# RF_Test.net
KiCad netlist of a schematic drawn in EAGLE
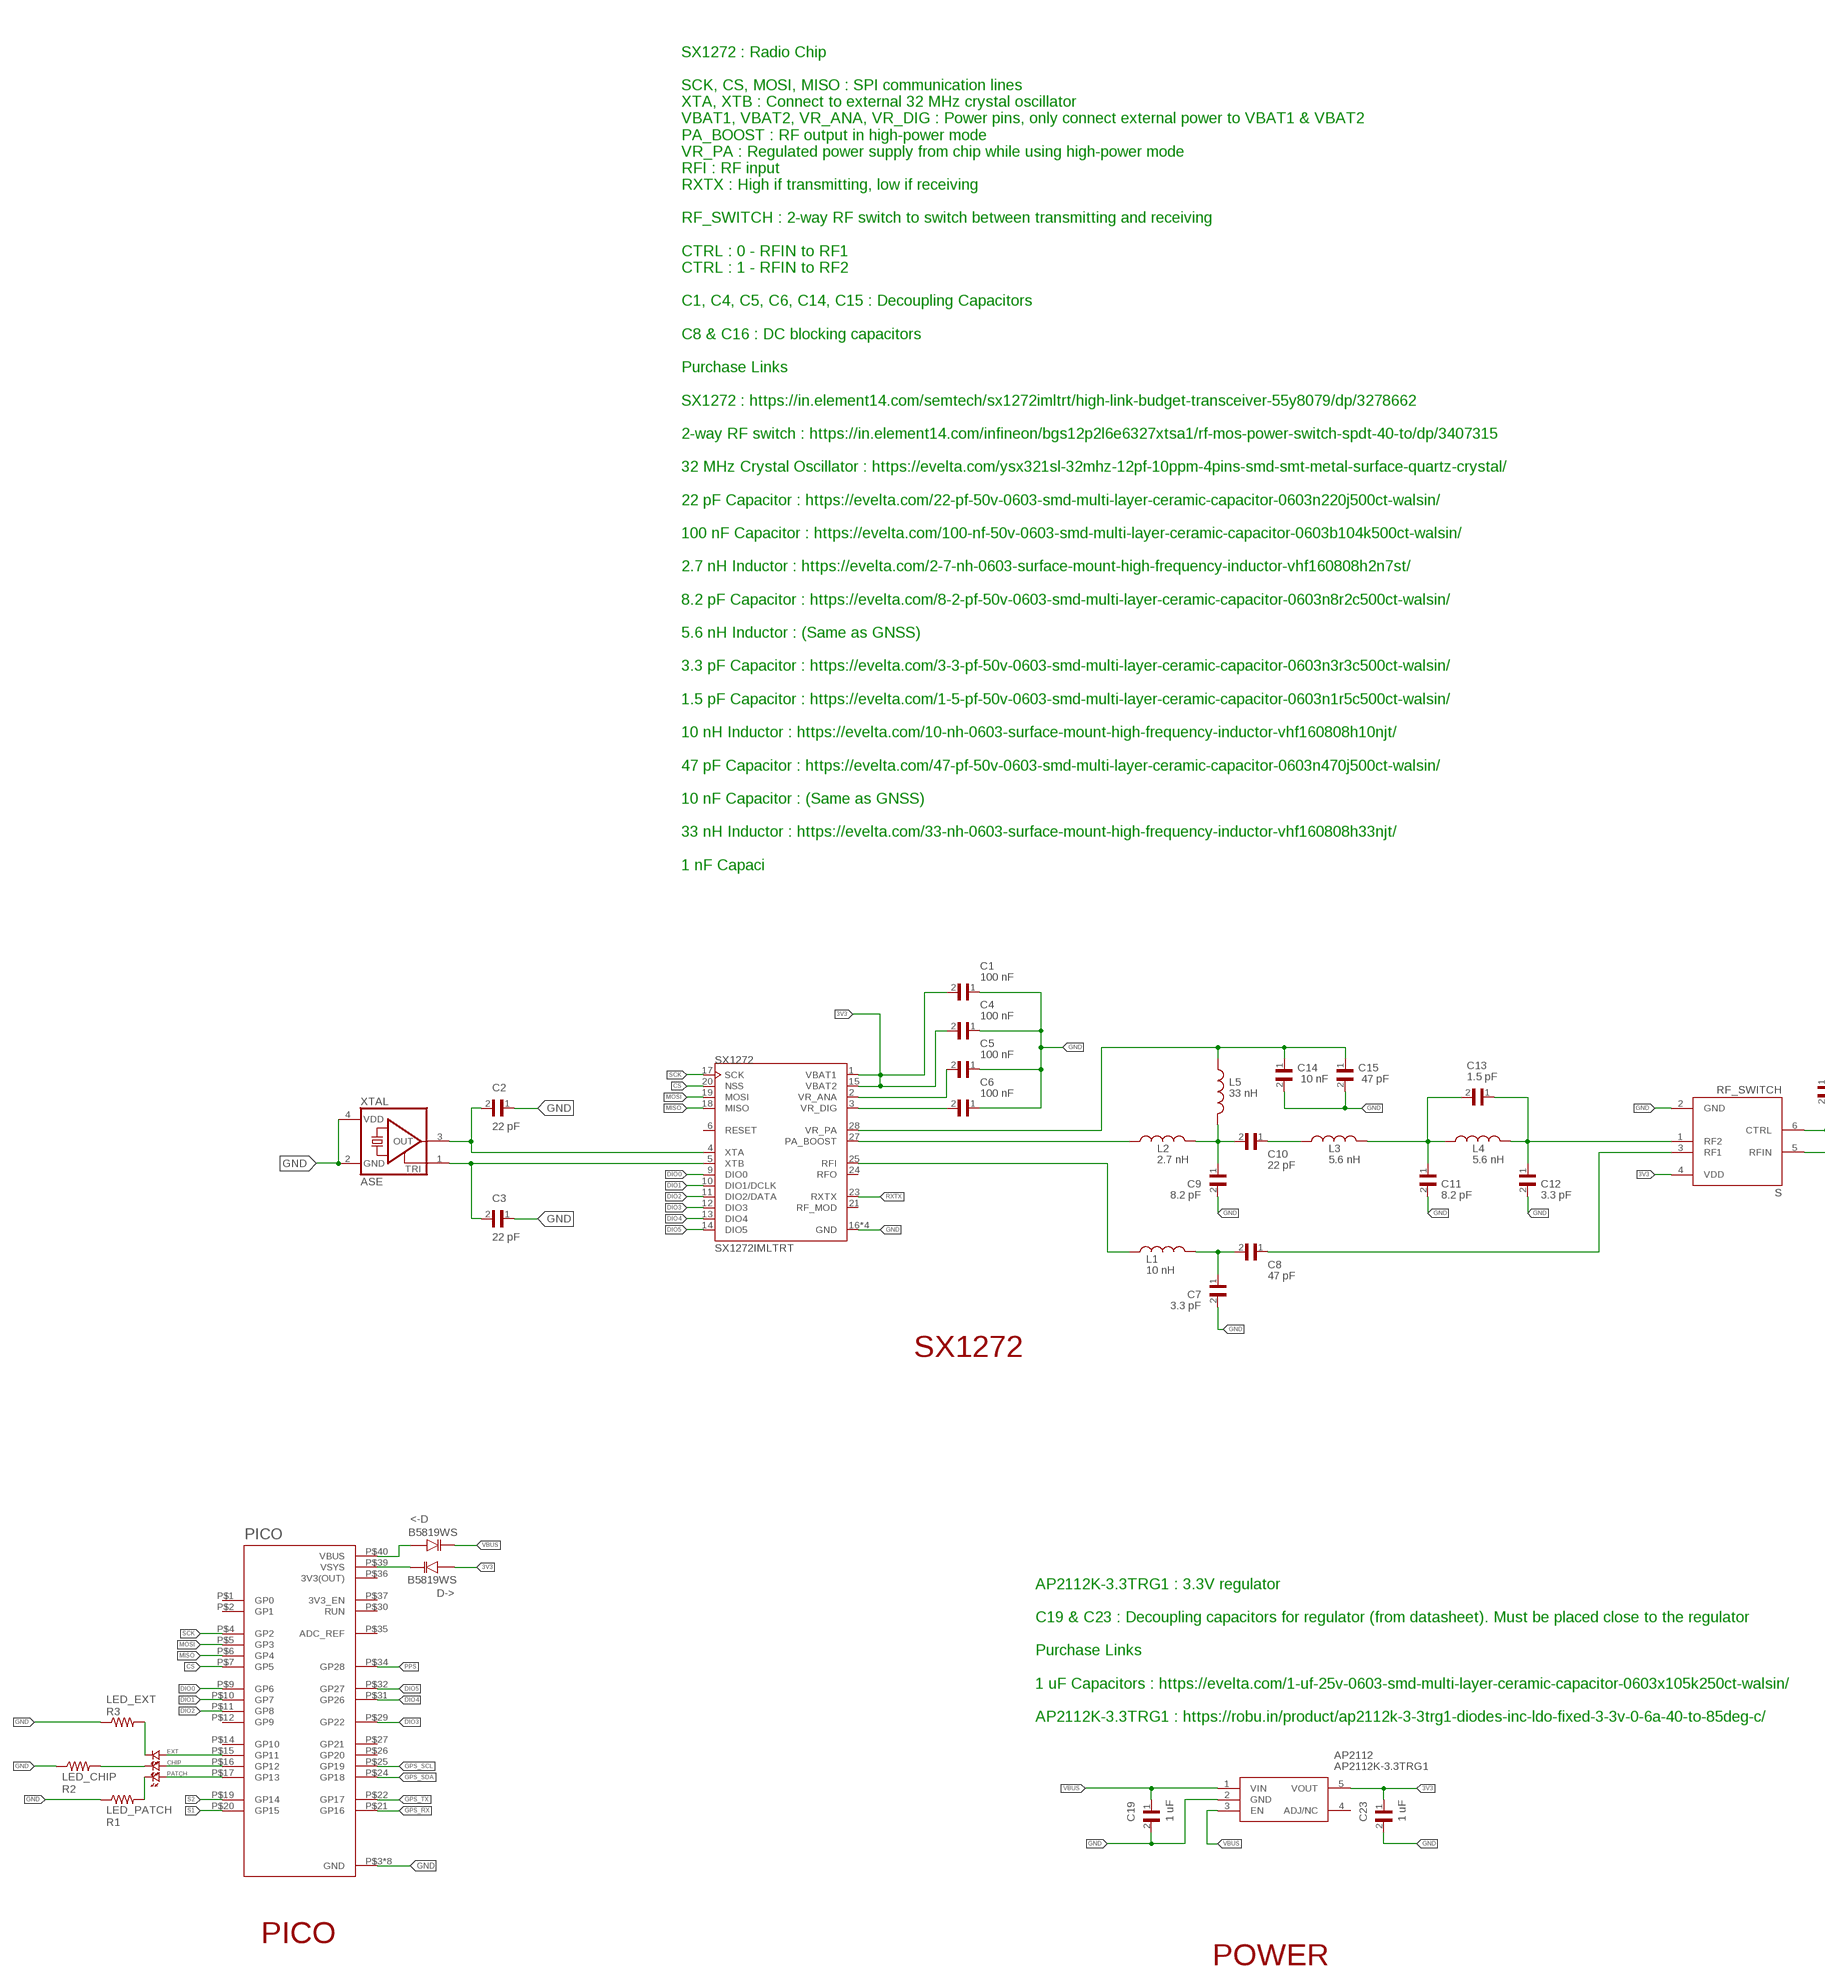
[diagram p0: schematic, sheet 1, part 1 of 2]
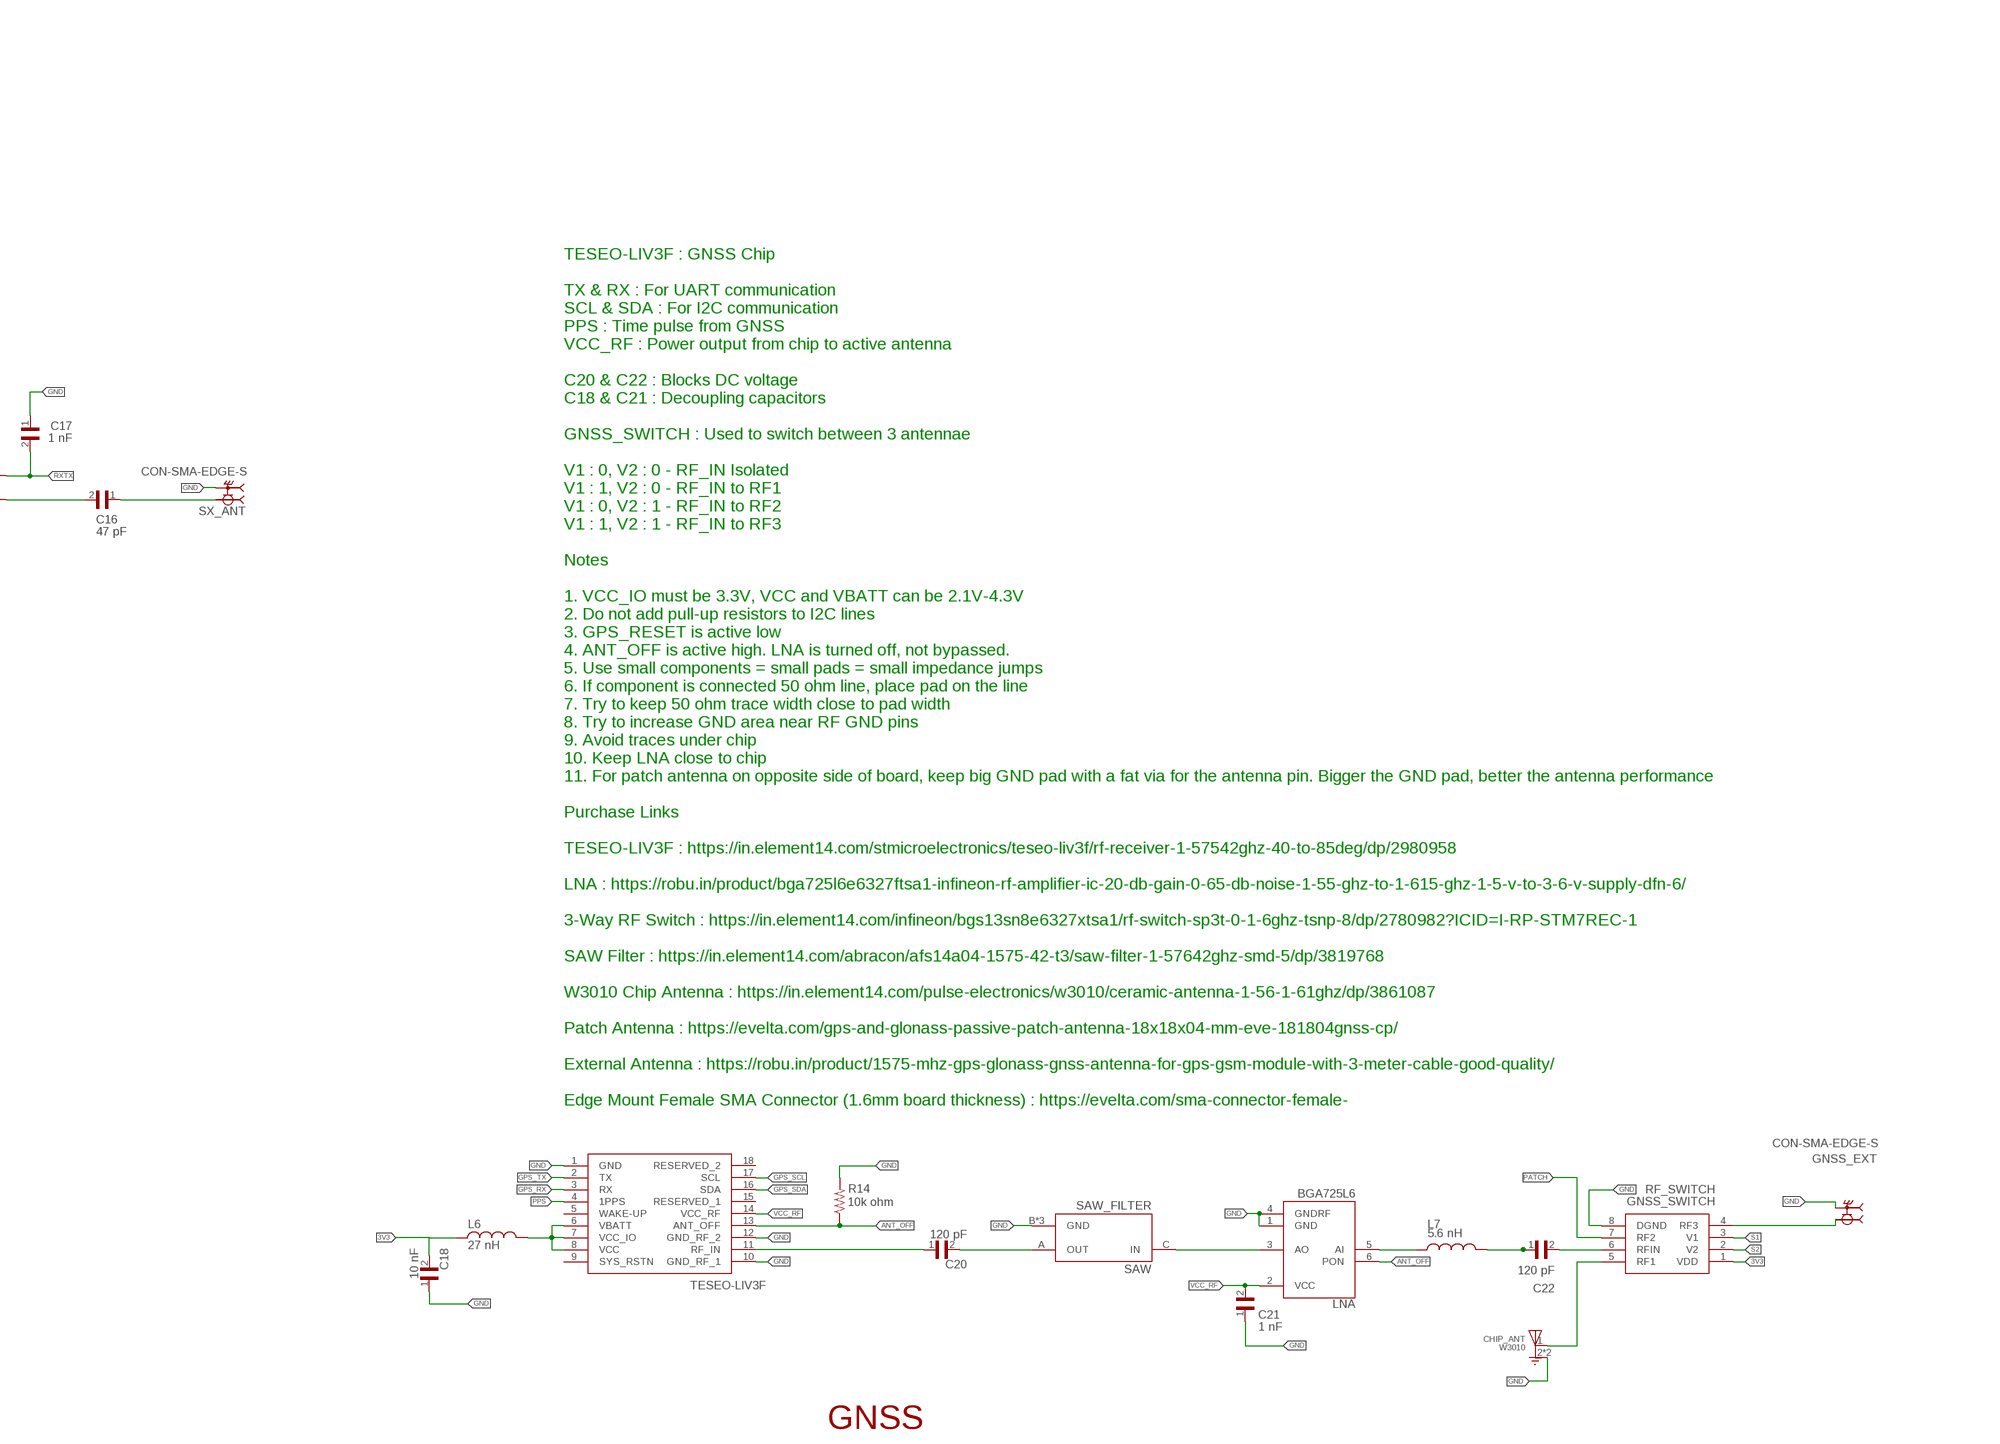
[diagram p1: schematic, sheet 1, part 2 of 2]

(export (version "E")
  (design (tool "Eeschema 10.0.6"))
  (components
    (comp (ref "<-D")
      (value "B5819WS")
      (footprint "eagle-import:SOD2512X116N")
      (fields (field (name "MF") "Diodes Inc.") (field (name "MP") "ZMV829BTA"))
      (libsource (lib "eagle-import") (part "ZMV829BTA"))
    )
    (comp (ref "AP2112")
      (value "AP2112K-3.3TRG1")
      (footprint "eagle-import:SOT95P282X130-5N")
      (fields (field (name "MOUSER_PART_NUMBER") "621-AP2112K-3.3TRG1"))
      (libsource (lib "eagle-import") (part "AP2112K-3.3TRG1"))
    )
    (comp (ref "C1")
      (value "100 nF")
      (footprint "eagle-import:CAPC1608X90")
      (fields (field (name "MF") "Yageo") (field (name "MP") "CC0603KRX7R9BB104"))
      (libsource (lib "eagle-import") (part "CC0603KRX7R9BB104"))
    )
    (comp (ref "C2")
      (value "22 pF")
      (footprint "eagle-import:CAPC1608X90")
      (fields (field (name "MF") "Yageo") (field (name "MP") "CC0603KRX7R9BB104"))
      (libsource (lib "eagle-import") (part "CC0603KRX7R9BB104"))
    )
    (comp (ref "C3")
      (value "22 pF")
      (footprint "eagle-import:CAPC1608X90")
      (fields (field (name "MF") "Yageo") (field (name "MP") "CC0603KRX7R9BB104"))
      (libsource (lib "eagle-import") (part "CC0603KRX7R9BB104"))
    )
    (comp (ref "C4")
      (value "100 nF")
      (footprint "eagle-import:CAPC1608X90")
      (fields (field (name "MF") "Yageo") (field (name "MP") "CC0603KRX7R9BB104"))
      (libsource (lib "eagle-import") (part "CC0603KRX7R9BB104"))
    )
    (comp (ref "C5")
      (value "100 nF")
      (footprint "eagle-import:CAPC1608X90")
      (fields (field (name "MF") "Yageo") (field (name "MP") "CC0603KRX7R9BB104"))
      (libsource (lib "eagle-import") (part "CC0603KRX7R9BB104"))
    )
    (comp (ref "C6")
      (value "100 nF")
      (footprint "eagle-import:CAPC1608X90")
      (fields (field (name "MF") "Yageo") (field (name "MP") "CC0603KRX7R9BB104"))
      (libsource (lib "eagle-import") (part "CC0603KRX7R9BB104"))
    )
    (comp (ref "C7")
      (value "3.3 pF")
      (footprint "eagle-import:CAPC1608X90")
      (fields (field (name "MF") "Yageo") (field (name "MP") "CC0603KRX7R9BB104"))
      (libsource (lib "eagle-import") (part "CC0603KRX7R9BB104"))
    )
    (comp (ref "C8")
      (value "47 pF")
      (footprint "eagle-import:CAPC1608X90")
      (fields (field (name "MF") "Yageo") (field (name "MP") "CC0603KRX7R9BB104"))
      (libsource (lib "eagle-import") (part "CC0603KRX7R9BB104"))
    )
    (comp (ref "C9")
      (value "8.2 pF")
      (footprint "eagle-import:CAPC1608X90")
      (fields (field (name "MF") "Yageo") (field (name "MP") "CC0603KRX7R9BB104"))
      (libsource (lib "eagle-import") (part "CC0603KRX7R9BB104"))
    )
    (comp (ref "C10")
      (value "22 pF")
      (footprint "eagle-import:CAPC1608X90")
      (fields (field (name "MF") "Yageo") (field (name "MP") "CC0603KRX7R9BB104"))
      (libsource (lib "eagle-import") (part "CC0603KRX7R9BB104"))
    )
    (comp (ref "C11")
      (value "8.2 pF")
      (footprint "eagle-import:CAPC1608X90")
      (fields (field (name "MF") "Yageo") (field (name "MP") "CC0603KRX7R9BB104"))
      (libsource (lib "eagle-import") (part "CC0603KRX7R9BB104"))
    )
    (comp (ref "C12")
      (value "3.3 pF")
      (footprint "eagle-import:CAPC1608X90")
      (fields (field (name "MF") "Yageo") (field (name "MP") "CC0603KRX7R9BB104"))
      (libsource (lib "eagle-import") (part "CC0603KRX7R9BB104"))
    )
    (comp (ref "C13")
      (value "1.5 pF")
      (footprint "eagle-import:CAPC1608X90")
      (fields (field (name "MF") "Yageo") (field (name "MP") "CC0603KRX7R9BB104"))
      (libsource (lib "eagle-import") (part "CC0603KRX7R9BB104"))
    )
    (comp (ref "C14")
      (value "10 nF")
      (footprint "eagle-import:CAPC1608X90")
      (fields (field (name "MF") "Yageo") (field (name "MP") "CC0603KRX7R9BB104"))
      (libsource (lib "eagle-import") (part "CC0603KRX7R9BB104"))
    )
    (comp (ref "C15")
      (value "47 pF")
      (footprint "eagle-import:CAPC1608X90")
      (fields (field (name "MF") "Yageo") (field (name "MP") "CC0603KRX7R9BB104"))
      (libsource (lib "eagle-import") (part "CC0603KRX7R9BB104"))
    )
    (comp (ref "C16")
      (value "47 pF")
      (footprint "eagle-import:CAPC1608X90")
      (fields (field (name "MF") "Yageo") (field (name "MP") "CC0603KRX7R9BB104"))
      (libsource (lib "eagle-import") (part "CC0603KRX7R9BB104"))
    )
    (comp (ref "C17")
      (value "1 nF")
      (footprint "eagle-import:CAPC1608X90")
      (fields (field (name "MF") "Yageo") (field (name "MP") "CC0603KRX7R9BB104"))
      (libsource (lib "eagle-import") (part "CC0603KRX7R9BB104"))
    )
    (comp (ref "C18")
      (value "10 nF")
      (footprint "eagle-import:CAPC1608X90")
      (fields (field (name "MF") "Yageo") (field (name "MP") "CC0603KRX7R9BB104"))
      (libsource (lib "eagle-import") (part "CC0603KRX7R9BB104"))
    )
    (comp (ref "C19")
      (value "1 uF")
      (footprint "eagle-import:CAPC1608X90")
      (fields (field (name "MF") "Yageo") (field (name "MP") "CC0603KRX7R9BB104"))
      (libsource (lib "eagle-import") (part "CC0603KRX7R9BB104"))
    )
    (comp (ref "C20")
      (value "120 pF")
      (footprint "eagle-import:CAPC1608X90")
      (fields (field (name "MF") "Yageo") (field (name "MP") "CC0603KRX7R9BB104"))
      (libsource (lib "eagle-import") (part "CC0603KRX7R9BB104"))
    )
    (comp (ref "C21")
      (value "1 nF")
      (footprint "eagle-import:CAPC1608X90")
      (fields (field (name "MF") "Yageo") (field (name "MP") "CC0603KRX7R9BB104"))
      (libsource (lib "eagle-import") (part "CC0603KRX7R9BB104"))
    )
    (comp (ref "C22")
      (value "120 pF")
      (footprint "eagle-import:CAPC1608X90")
      (fields (field (name "MF") "Yageo") (field (name "MP") "CC0603KRX7R9BB104"))
      (libsource (lib "eagle-import") (part "CC0603KRX7R9BB104"))
    )
    (comp (ref "C23")
      (value "1 uF")
      (footprint "eagle-import:CAPC1608X90")
      (fields (field (name "MF") "Yageo") (field (name "MP") "CC0603KRX7R9BB104"))
      (libsource (lib "eagle-import") (part "CC0603KRX7R9BB104"))
    )
    (comp (ref "CHIP")
      (value "LED.0603")
      (footprint "eagle-import:0603.LED")
      (libsource (lib "eagle-import") (part "LED.0603"))
    )
    (comp (ref "CHIP_ANT")
      (value "W3010")
      (footprint "eagle-import:XCVR_W3010")
      (fields (field (name "MF") "PulseLarsen Antennas"))
      (libsource (lib "eagle-import") (part "W3010"))
    )
    (comp (ref "D->")
      (value "B5819WS")
      (footprint "eagle-import:SOD2512X116N")
      (fields (field (name "MF") "Diodes Inc.") (field (name "MP") "ZMV829BTA"))
      (libsource (lib "eagle-import") (part "ZMV829BTA"))
    )
    (comp (ref "EXT")
      (value "LED.0603")
      (footprint "eagle-import:0603.LED")
      (libsource (lib "eagle-import") (part "LED.0603"))
    )
    (comp (ref "GNSS")
      (value "TESEO-LIV3F")
      (footprint "eagle-import:SON110P970X1010X230-18N")
      (fields (field (name "MF") "STMicroelectronics"))
      (libsource (lib "eagle-import") (part "TESEO-LIV3F"))
    )
    (comp (ref "GNSS_EXT")
      (value "CON-SMA-EDGE-S")
      (footprint "eagle-import:RFSOLUTIONS_CON-SMA-EDGE-S")
      (fields (field (name "MF") "RF Solutions"))
      (libsource (lib "eagle-import") (part "CON-SMA-EDGE-S"))
    )
    (comp (ref "GNSS_SWITCH")
      (value "RF_SWITCH")
      (footprint "eagle-import:BGS13SN8E6327XTSA1")
      (fields (field (name "MANUFACTURER_PART_NUMBER") "BGS13SN8E6327XTSA1"))
      (libsource (lib "eagle-import") (part "BGS13SN8E6327XTSA1"))
    )
    (comp (ref "L1")
      (value "10 nH")
      (footprint "eagle-import:INDC1608X90N")
      (fields (field (name "MF") "Murata Electronics") (field (name "MP") "LQM18FN100M00D"))
      (libsource (lib "eagle-import") (part "LQM18FN100M00D"))
    )
    (comp (ref "L2")
      (value "2.7 nH")
      (footprint "eagle-import:INDC1608X90N")
      (fields (field (name "MF") "Murata Electronics") (field (name "MP") "LQM18FN100M00D"))
      (libsource (lib "eagle-import") (part "LQM18FN100M00D"))
    )
    (comp (ref "L3")
      (value "5.6 nH")
      (footprint "eagle-import:INDC1608X90N")
      (fields (field (name "MF") "Murata Electronics") (field (name "MP") "LQM18FN100M00D"))
      (libsource (lib "eagle-import") (part "LQM18FN100M00D"))
    )
    (comp (ref "L4")
      (value "5.6 nH")
      (footprint "eagle-import:INDC1608X90N")
      (fields (field (name "MF") "Murata Electronics") (field (name "MP") "LQM18FN100M00D"))
      (libsource (lib "eagle-import") (part "LQM18FN100M00D"))
    )
    (comp (ref "L5")
      (value "33 nH")
      (footprint "eagle-import:INDC1608X90N")
      (fields (field (name "MF") "Murata Electronics") (field (name "MP") "LQM18FN100M00D"))
      (libsource (lib "eagle-import") (part "LQM18FN100M00D"))
    )
    (comp (ref "L6")
      (value "27 nH")
      (footprint "eagle-import:INDC1608X90N")
      (fields (field (name "MF") "Murata Electronics") (field (name "MP") "LQM18FN100M00D"))
      (libsource (lib "eagle-import") (part "LQM18FN100M00D"))
    )
    (comp (ref "L7")
      (value "5.6 nH")
      (footprint "eagle-import:INDC1608X90N")
      (fields (field (name "MF") "Murata Electronics") (field (name "MP") "LQM18FN100M00D"))
      (libsource (lib "eagle-import") (part "LQM18FN100M00D"))
    )
    (comp (ref "LNA")
      (value "BGA725L6")
      (footprint "eagle-import:AMP_BGA725L6E6327FTSA1")
      (fields (field (name "MF") "Infineon Technologies") (field (name "MP") "BGA725L6E6327FTSA1"))
      (libsource (lib "eagle-import") (part "BGA725L6E6327FTSA1"))
    )
    (comp (ref "PATCH")
      (value "LED.0603")
      (footprint "eagle-import:0603.LED")
      (libsource (lib "eagle-import") (part "LED.0603"))
    )
    (comp (ref "PICO")
      (value "RASPBERRY_PICO-NO_DEBUG")
      (footprint "eagle-import:PICO-PKG-NO_DEBUG")
      (libsource (lib "eagle-import") (part "RASPBERRY_PICO-NO_DEBUG"))
    )
    (comp (ref "R1")
      (value "LED_PATCH")
      (footprint "eagle-import:RESC1608X50N")
      (fields
        (field (name "COMMENT") "2-1879338-7")
        (field (name "MF") "TE Connectivity")
        (field (name "MP") "CPF0603F49K9C1")
      )
      (libsource (lib "eagle-import") (part "CPF0603F49K9C1"))
    )
    (comp (ref "R2")
      (value "LED_CHIP")
      (footprint "eagle-import:RESC1608X50N")
      (fields
        (field (name "COMMENT") "2-1879338-7")
        (field (name "MF") "TE Connectivity")
        (field (name "MP") "CPF0603F49K9C1")
      )
      (libsource (lib "eagle-import") (part "CPF0603F49K9C1"))
    )
    (comp (ref "R3")
      (value "LED_EXT")
      (footprint "eagle-import:RESC1608X50N")
      (fields
        (field (name "COMMENT") "2-1879338-7")
        (field (name "MF") "TE Connectivity")
        (field (name "MP") "CPF0603F49K9C1")
      )
      (libsource (lib "eagle-import") (part "CPF0603F49K9C1"))
    )
    (comp (ref "R14")
      (value "10k ohm")
      (footprint "eagle-import:RESC1608X50N")
      (fields
        (field (name "COMMENT") "2-1879338-7")
        (field (name "MF") "TE Connectivity")
        (field (name "MP") "CPF0603F49K9C1")
      )
      (libsource (lib "eagle-import") (part "CPF0603F49K9C1"))
    )
    (comp (ref "S")
      (value "RF_SWITCH")
      (footprint "eagle-import:SW_BGS12P2L6E6327XTSA1")
      (fields (field (name "MF") "Infineon Technologies") (field (name "MP") "BGS12P2L6E6327XTSA1"))
      (libsource (lib "eagle-import") (part "BGS12P2L6E6327XTSA1"))
    )
    (comp (ref "SAW")
      (value "SAW_FILTER")
      (footprint "eagle-import:FIL_AFS14A04-1575.42-T3")
      (fields (field (name "MANUFACTURER") "Abracon"))
      (libsource (lib "eagle-import") (part "AFS14A04-1575.42-T3"))
    )
    (comp (ref "SX1272")
      (value "SX1272IMLTRT")
      (footprint "eagle-import:QFN65P600X600X100-29N")
      (fields (field (name "MF") "Semtech"))
      (libsource (lib "eagle-import") (part "SX1272IMLTRT"))
    )
    (comp (ref "SX_ANT")
      (value "CON-SMA-EDGE-S")
      (footprint "eagle-import:RFSOLUTIONS_CON-SMA-EDGE-S")
      (fields (field (name "MF") "RF Solutions"))
      (libsource (lib "eagle-import") (part "CON-SMA-EDGE-S"))
    )
    (comp (ref "XTAL")
      (value "ASE")
      (footprint "eagle-import:ASE")
      (libsource (lib "eagle-import") (part "ASE"))
    )
  )
  (nets
    (net (code "1") (name "/3V3(OUT)") (class "Default")
      (node (ref "PICO") (pin "P$36") (pinfunction "3V3(OUT)_P$36") (pintype "power_in"))
    )
    (net (code "2") (name "3V3") (class "Default")
      (node (ref "AP2112") (pin "5") (pinfunction "VOUT_5") (pintype "bidirectional"))
      (node (ref "C1") (pin "2") (pinfunction "2_2") (pintype "passive"))
      (node (ref "C18") (pin "2") (pinfunction "2_2") (pintype "passive"))
      (node (ref "C23") (pin "1") (pinfunction "1_1") (pintype "passive"))
      (node (ref "C4") (pin "2") (pinfunction "2_2") (pintype "passive"))
      (node (ref "D->") (pin "A") (pinfunction "A_A") (pintype "passive"))
      (node (ref "GNSS_SWITCH") (pin "1") (pinfunction "VDD_1") (pintype "bidirectional"))
      (node (ref "L6") (pin "1") (pinfunction "1_1") (pintype "passive"))
      (node (ref "S") (pin "4") (pinfunction "VDD_4") (pintype "power_in"))
      (node (ref "SX1272") (pin "1") (pinfunction "VBAT1_1") (pintype "power_in"))
      (node (ref "SX1272") (pin "15") (pinfunction "VBAT2_15") (pintype "power_in"))
    )
    (net (code "3") (name "ANT_OFF") (class "Default")
      (node (ref "GNSS") (pin "13") (pinfunction "ANT_OFF_13") (pintype "bidirectional"))
      (node (ref "LNA") (pin "6") (pinfunction "PON_6") (pintype "input"))
      (node (ref "R14") (pin "1") (pinfunction "1_1") (pintype "passive"))
    )
    (net (code "4") (name "CS") (class "Default")
      (node (ref "PICO") (pin "P$7") (pinfunction "GP5_P$7") (pintype "bidirectional"))
      (node (ref "SX1272") (pin "20") (pinfunction "NSS_20") (pintype "input"))
    )
    (net (code "5") (name "DIO0") (class "Default")
      (node (ref "PICO") (pin "P$9") (pinfunction "GP6_P$9") (pintype "bidirectional"))
      (node (ref "SX1272") (pin "9") (pinfunction "DIO0_9") (pintype "bidirectional"))
    )
    (net (code "6") (name "DIO1") (class "Default")
      (node (ref "PICO") (pin "P$10") (pinfunction "GP7_P$10") (pintype "bidirectional"))
      (node (ref "SX1272") (pin "10") (pinfunction "DIO1/DCLK_10") (pintype "bidirectional"))
    )
    (net (code "7") (name "DIO2") (class "Default")
      (node (ref "PICO") (pin "P$11") (pinfunction "GP8_P$11") (pintype "bidirectional"))
      (node (ref "SX1272") (pin "11") (pinfunction "DIO2/DATA_11") (pintype "bidirectional"))
    )
    (net (code "8") (name "DIO3") (class "Default")
      (node (ref "PICO") (pin "P$29") (pinfunction "GP22_P$29") (pintype "bidirectional"))
      (node (ref "SX1272") (pin "12") (pinfunction "DIO3_12") (pintype "bidirectional"))
    )
    (net (code "9") (name "DIO4") (class "Default")
      (node (ref "PICO") (pin "P$31") (pinfunction "GP26_P$31") (pintype "bidirectional"))
      (node (ref "SX1272") (pin "13") (pinfunction "DIO4_13") (pintype "bidirectional"))
    )
    (net (code "10") (name "DIO5") (class "Default")
      (node (ref "PICO") (pin "P$32") (pinfunction "GP27_P$32") (pintype "bidirectional"))
      (node (ref "SX1272") (pin "14") (pinfunction "DIO5_14") (pintype "bidirectional"))
    )
    (net (code "11") (name "GND") (class "Default")
      (node (ref "AP2112") (pin "2") (pinfunction "GND_2") (pintype "bidirectional"))
      (node (ref "C1") (pin "1") (pinfunction "1_1") (pintype "passive"))
      (node (ref "C11") (pin "2") (pinfunction "2_2") (pintype "passive"))
      (node (ref "C12") (pin "2") (pinfunction "2_2") (pintype "passive"))
      (node (ref "C14") (pin "2") (pinfunction "2_2") (pintype "passive"))
      (node (ref "C15") (pin "2") (pinfunction "2_2") (pintype "passive"))
      (node (ref "C17") (pin "1") (pinfunction "1_1") (pintype "passive"))
      (node (ref "C18") (pin "1") (pinfunction "1_1") (pintype "passive"))
      (node (ref "C19") (pin "2") (pinfunction "2_2") (pintype "passive"))
      (node (ref "C2") (pin "1") (pinfunction "1_1") (pintype "passive"))
      (node (ref "C21") (pin "1") (pinfunction "1_1") (pintype "passive"))
      (node (ref "C23") (pin "2") (pinfunction "2_2") (pintype "passive"))
      (node (ref "C3") (pin "1") (pinfunction "1_1") (pintype "passive"))
      (node (ref "C4") (pin "1") (pinfunction "1_1") (pintype "passive"))
      (node (ref "C5") (pin "1") (pinfunction "1_1") (pintype "passive"))
      (node (ref "C6") (pin "1") (pinfunction "1_1") (pintype "passive"))
      (node (ref "C7") (pin "2") (pinfunction "2_2") (pintype "passive"))
      (node (ref "C9") (pin "2") (pinfunction "2_2") (pintype "passive"))
      (node (ref "CHIP_ANT") (pin "2") (pinfunction "GND_2") (pintype "power_in"))
      (node (ref "CHIP_ANT") (pin "3") (pinfunction "GND_3") (pintype "power_in"))
      (node (ref "GNSS") (pin "1") (pinfunction "GND_1") (pintype "bidirectional"))
      (node (ref "GNSS") (pin "10") (pinfunction "GND_RF_1_10") (pintype "bidirectional"))
      (node (ref "GNSS") (pin "12") (pinfunction "GND_RF_2_12") (pintype "bidirectional"))
      (node (ref "GNSS_EXT") (pin "G1") (pinfunction "2_G1") (pintype "passive"))
      (node (ref "GNSS_EXT") (pin "G2") (pinfunction "2_G2") (pintype "passive"))
      (node (ref "GNSS_EXT") (pin "G3") (pinfunction "2_G3") (pintype "passive"))
      (node (ref "GNSS_EXT") (pin "G4") (pinfunction "2_G4") (pintype "passive"))
      (node (ref "GNSS_SWITCH") (pin "8") (pinfunction "DGND_8") (pintype "bidirectional"))
      (node (ref "LNA") (pin "1") (pinfunction "GND_1") (pintype "power_in"))
      (node (ref "LNA") (pin "4") (pinfunction "GNDRF_4") (pintype "power_in"))
      (node (ref "PICO") (pin "P$13") (pinfunction "GND_P$13") (pintype "power_in"))
      (node (ref "PICO") (pin "P$18") (pinfunction "GND_P$18") (pintype "power_in"))
      (node (ref "PICO") (pin "P$23") (pinfunction "GND_P$23") (pintype "power_in"))
      (node (ref "PICO") (pin "P$28") (pinfunction "GND_P$28") (pintype "power_in"))
      (node (ref "PICO") (pin "P$3") (pinfunction "GND_P$3") (pintype "power_in"))
      (node (ref "PICO") (pin "P$33") (pinfunction "GND_P$33") (pintype "power_in"))
      (node (ref "PICO") (pin "P$38") (pinfunction "GND_P$38") (pintype "power_in"))
      (node (ref "PICO") (pin "P$8") (pinfunction "GND_P$8") (pintype "power_in"))
      (node (ref "R1") (pin "1") (pinfunction "1_1") (pintype "passive"))
      (node (ref "R14") (pin "2") (pinfunction "2_2") (pintype "passive"))
      (node (ref "R2") (pin "1") (pinfunction "1_1") (pintype "passive"))
      (node (ref "R3") (pin "1") (pinfunction "1_1") (pintype "passive"))
      (node (ref "S") (pin "2") (pinfunction "GND_2") (pintype "power_in"))
      (node (ref "SAW") (pin "B") (pinfunction "GND_B") (pintype "power_in"))
      (node (ref "SAW") (pin "D") (pinfunction "GND_D") (pintype "power_in"))
      (node (ref "SAW") (pin "E") (pinfunction "GND_E") (pintype "power_in"))
      (node (ref "SX1272") (pin "16") (pinfunction "GND_16") (pintype "power_in"))
      (node (ref "SX1272") (pin "22") (pinfunction "GND_22") (pintype "power_in"))
      (node (ref "SX1272") (pin "26") (pinfunction "GND_26") (pintype "power_in"))
      (node (ref "SX1272") (pin "29") (pinfunction "GND_29") (pintype "power_in"))
      (node (ref "SX_ANT") (pin "G1") (pinfunction "2_G1") (pintype "passive"))
      (node (ref "SX_ANT") (pin "G2") (pinfunction "2_G2") (pintype "passive"))
      (node (ref "SX_ANT") (pin "G3") (pinfunction "2_G3") (pintype "passive"))
      (node (ref "SX_ANT") (pin "G4") (pinfunction "2_G4") (pintype "passive"))
      (node (ref "XTAL") (pin "2") (pinfunction "GND_2") (pintype "power_in"))
      (node (ref "XTAL") (pin "4") (pinfunction "VDD_4") (pintype "power_in"))
    )
    (net (code "12") (name "GPS_RX") (class "Default")
      (node (ref "GNSS") (pin "3") (pinfunction "RX_3") (pintype "bidirectional"))
      (node (ref "PICO") (pin "P$21") (pinfunction "GP16_P$21") (pintype "bidirectional"))
    )
    (net (code "13") (name "GPS_SCL") (class "Default")
      (node (ref "GNSS") (pin "17") (pinfunction "SCL_17") (pintype "bidirectional"))
      (node (ref "PICO") (pin "P$25") (pinfunction "GP19_P$25") (pintype "bidirectional"))
    )
    (net (code "14") (name "GPS_SDA") (class "Default")
      (node (ref "GNSS") (pin "16") (pinfunction "SDA_16") (pintype "bidirectional"))
      (node (ref "PICO") (pin "P$24") (pinfunction "GP18_P$24") (pintype "bidirectional"))
    )
    (net (code "15") (name "GPS_TX") (class "Default")
      (node (ref "GNSS") (pin "2") (pinfunction "TX_2") (pintype "bidirectional"))
      (node (ref "PICO") (pin "P$22") (pinfunction "GP17_P$22") (pintype "bidirectional"))
    )
    (net (code "16") (name "MISO") (class "Default")
      (node (ref "PICO") (pin "P$6") (pinfunction "GP4_P$6") (pintype "bidirectional"))
      (node (ref "SX1272") (pin "18") (pinfunction "MISO_18") (pintype "output"))
    )
    (net (code "17") (name "MOSI") (class "Default")
      (node (ref "PICO") (pin "P$5") (pinfunction "GP3_P$5") (pintype "bidirectional"))
      (node (ref "SX1272") (pin "19") (pinfunction "MOSI_19") (pintype "input"))
    )
    (net (code "18") (name "Net-(C7-Pad1)") (class "Default")
      (node (ref "C7") (pin "1") (pinfunction "1_1") (pintype "passive"))
      (node (ref "C8") (pin "2") (pinfunction "2_2") (pintype "passive"))
      (node (ref "L1") (pin "2") (pinfunction "2_2") (pintype "passive"))
    )
    (net (code "19") (name "Net-(C10-Pad1)") (class "Default")
      (node (ref "C10") (pin "1") (pinfunction "1_1") (pintype "passive"))
      (node (ref "L3") (pin "1") (pinfunction "1_1") (pintype "passive"))
    )
    (net (code "20") (name "Net-(C10-Pad2)") (class "Default")
      (node (ref "C10") (pin "2") (pinfunction "2_2") (pintype "passive"))
      (node (ref "C9") (pin "1") (pinfunction "1_1") (pintype "passive"))
      (node (ref "L2") (pin "2") (pinfunction "2_2") (pintype "passive"))
      (node (ref "L5") (pin "2") (pinfunction "2_2") (pintype "passive"))
    )
    (net (code "21") (name "Net-(C11-Pad1)") (class "Default")
      (node (ref "C11") (pin "1") (pinfunction "1_1") (pintype "passive"))
      (node (ref "C13") (pin "2") (pinfunction "2_2") (pintype "passive"))
      (node (ref "L3") (pin "2") (pinfunction "2_2") (pintype "passive"))
      (node (ref "L4") (pin "1") (pinfunction "1_1") (pintype "passive"))
    )
    (net (code "22") (name "Net-(C16-Pad1)") (class "Default")
      (node (ref "C16") (pin "1") (pinfunction "1_1") (pintype "passive"))
      (node (ref "SX_ANT") (pin "1") (pinfunction "1_1") (pintype "passive"))
    )
    (net (code "23") (name "Net-(C22-Pad1)") (class "Default")
      (node (ref "C22") (pin "1") (pinfunction "1_1") (pintype "passive"))
      (node (ref "L7") (pin "2") (pinfunction "2_2") (pintype "passive"))
    )
    (net (code "24") (name "Net-(CHIP-1)") (class "Default")
      (node (ref "CHIP") (pin "P$1") (pinfunction "1_P$1") (pintype "bidirectional"))
      (node (ref "PICO") (pin "P$16") (pinfunction "GP12_P$16") (pintype "bidirectional"))
    )
    (net (code "25") (name "Net-(CHIP-2)") (class "Default")
      (node (ref "CHIP") (pin "P$2") (pinfunction "2_P$2") (pintype "bidirectional"))
      (node (ref "R2") (pin "2") (pinfunction "2_2") (pintype "passive"))
    )
    (net (code "26") (name "Net-(CHIP_ANT-FEEDING)") (class "Default")
      (node (ref "CHIP_ANT") (pin "1") (pinfunction "FEEDING_1") (pintype "passive"))
      (node (ref "GNSS_SWITCH") (pin "5") (pinfunction "RF1_5") (pintype "bidirectional"))
    )
    (net (code "27") (name "Net-(EXT-1)") (class "Default")
      (node (ref "EXT") (pin "P$1") (pinfunction "1_P$1") (pintype "bidirectional"))
      (node (ref "PICO") (pin "P$15") (pinfunction "GP11_P$15") (pintype "bidirectional"))
    )
    (net (code "28") (name "Net-(EXT-2)") (class "Default")
      (node (ref "EXT") (pin "P$2") (pinfunction "2_P$2") (pintype "bidirectional"))
      (node (ref "R3") (pin "2") (pinfunction "2_2") (pintype "passive"))
    )
    (net (code "29") (name "Net-(GNSS-RF_IN)") (class "Default")
      (node (ref "C20") (pin "1") (pinfunction "1_1") (pintype "passive"))
      (node (ref "GNSS") (pin "11") (pinfunction "RF_IN_11") (pintype "bidirectional"))
    )
    (net (code "30") (name "Net-(GNSS-VBATT)") (class "Default")
      (node (ref "GNSS") (pin "6") (pinfunction "VBATT_6") (pintype "bidirectional"))
      (node (ref "GNSS") (pin "7") (pinfunction "VCC_IO_7") (pintype "bidirectional"))
      (node (ref "GNSS") (pin "8") (pinfunction "VCC_8") (pintype "bidirectional"))
      (node (ref "L6") (pin "2") (pinfunction "2_2") (pintype "passive"))
    )
    (net (code "31") (name "Net-(GNSS_SWITCH-RF3)") (class "Default")
      (node (ref "GNSS_EXT") (pin "1") (pinfunction "1_1") (pintype "passive"))
      (node (ref "GNSS_SWITCH") (pin "4") (pinfunction "RF3_4") (pintype "bidirectional"))
    )
    (net (code "32") (name "Net-(GNSS_SWITCH-RFIN)") (class "Default")
      (node (ref "C22") (pin "2") (pinfunction "2_2") (pintype "passive"))
      (node (ref "GNSS_SWITCH") (pin "6") (pinfunction "RFIN_6") (pintype "bidirectional"))
    )
    (net (code "33") (name "Net-(LNA-AI)") (class "Default")
      (node (ref "L7") (pin "1") (pinfunction "1_1") (pintype "passive"))
      (node (ref "LNA") (pin "5") (pinfunction "AI_5") (pintype "input"))
    )
    (net (code "34") (name "Net-(LNA-AO)") (class "Default")
      (node (ref "LNA") (pin "3") (pinfunction "AO_3") (pintype "output"))
      (node (ref "SAW") (pin "C") (pinfunction "IN_C") (pintype "input"))
    )
    (net (code "35") (name "Net-(PATCH-1)") (class "Default")
      (node (ref "PATCH") (pin "P$1") (pinfunction "1_P$1") (pintype "bidirectional"))
      (node (ref "PICO") (pin "P$17") (pinfunction "GP13_P$17") (pintype "bidirectional"))
    )
    (net (code "36") (name "Net-(PATCH-2)") (class "Default")
      (node (ref "PATCH") (pin "P$2") (pinfunction "2_P$2") (pintype "bidirectional"))
      (node (ref "R1") (pin "2") (pinfunction "2_2") (pintype "passive"))
    )
    (net (code "37") (name "Net-(PICO-VBUS)") (class "Default")
      (node (ref "<-D") (pin "A") (pinfunction "A_A") (pintype "passive"))
      (node (ref "PICO") (pin "P$40") (pinfunction "VBUS_P$40") (pintype "power_in"))
    )
    (net (code "38") (name "Net-(PICO-VSYS)") (class "Default")
      (node (ref "D->") (pin "K") (pinfunction "K_K") (pintype "passive"))
      (node (ref "PICO") (pin "P$39") (pinfunction "VSYS_P$39") (pintype "power_in"))
    )
    (net (code "39") (name "Net-(S-RF1)") (class "Default")
      (node (ref "C8") (pin "1") (pinfunction "1_1") (pintype "passive"))
      (node (ref "S") (pin "3") (pinfunction "RF1_3") (pintype "bidirectional"))
    )
    (net (code "40") (name "Net-(S-RF2)") (class "Default")
      (node (ref "C12") (pin "1") (pinfunction "1_1") (pintype "passive"))
      (node (ref "C13") (pin "1") (pinfunction "1_1") (pintype "passive"))
      (node (ref "L4") (pin "2") (pinfunction "2_2") (pintype "passive"))
      (node (ref "S") (pin "1") (pinfunction "RF2_1") (pintype "bidirectional"))
    )
    (net (code "41") (name "Net-(S-RFIN)") (class "Default")
      (node (ref "C16") (pin "2") (pinfunction "2_2") (pintype "passive"))
      (node (ref "S") (pin "5") (pinfunction "RFIN_5") (pintype "input"))
    )
    (net (code "42") (name "Net-(SAW-OUT)") (class "Default")
      (node (ref "C20") (pin "2") (pinfunction "2_2") (pintype "passive"))
      (node (ref "SAW") (pin "A") (pinfunction "OUT_A") (pintype "output"))
    )
    (net (code "43") (name "Net-(SX1272-PA_BOOST)") (class "Default")
      (node (ref "L2") (pin "1") (pinfunction "1_1") (pintype "passive"))
      (node (ref "SX1272") (pin "27") (pinfunction "PA_BOOST_27") (pintype "output"))
    )
    (net (code "44") (name "Net-(SX1272-RFI)") (class "Default")
      (node (ref "L1") (pin "1") (pinfunction "1_1") (pintype "passive"))
      (node (ref "SX1272") (pin "25") (pinfunction "RFI_25") (pintype "input"))
    )
    (net (code "45") (name "Net-(SX1272-VR_ANA)") (class "Default")
      (node (ref "C5") (pin "2") (pinfunction "2_2") (pintype "passive"))
      (node (ref "SX1272") (pin "2") (pinfunction "VR_ANA_2") (pintype "power_in"))
    )
    (net (code "46") (name "Net-(SX1272-VR_DIG)") (class "Default")
      (node (ref "C6") (pin "2") (pinfunction "2_2") (pintype "passive"))
      (node (ref "SX1272") (pin "3") (pinfunction "VR_DIG_3") (pintype "power_in"))
    )
    (net (code "47") (name "Net-(SX1272-VR_PA)") (class "Default")
      (node (ref "C14") (pin "1") (pinfunction "1_1") (pintype "passive"))
      (node (ref "C15") (pin "1") (pinfunction "1_1") (pintype "passive"))
      (node (ref "L5") (pin "1") (pinfunction "1_1") (pintype "passive"))
      (node (ref "SX1272") (pin "28") (pinfunction "VR_PA_28") (pintype "output"))
    )
    (net (code "48") (name "Net-(SX1272-XTA)") (class "Default")
      (node (ref "C2") (pin "2") (pinfunction "2_2") (pintype "passive"))
      (node (ref "SX1272") (pin "4") (pinfunction "XTA_4") (pintype "bidirectional"))
      (node (ref "XTAL") (pin "3") (pinfunction "OUT_3") (pintype "output"))
    )
    (net (code "49") (name "Net-(SX1272-XTB)") (class "Default")
      (node (ref "C3") (pin "2") (pinfunction "2_2") (pintype "passive"))
      (node (ref "SX1272") (pin "5") (pinfunction "XTB_5") (pintype "bidirectional"))
      (node (ref "XTAL") (pin "1") (pinfunction "TRI_1") (pintype "input"))
    )
    (net (code "50") (name "PATCH") (class "Default")
      (node (ref "GNSS_SWITCH") (pin "7") (pinfunction "RF2_7") (pintype "bidirectional"))
    )
    (net (code "51") (name "PPS") (class "Default")
      (node (ref "GNSS") (pin "4") (pinfunction "1PPS_4") (pintype "bidirectional"))
      (node (ref "PICO") (pin "P$34") (pinfunction "GP28_P$34") (pintype "bidirectional"))
    )
    (net (code "52") (name "RXTX") (class "Default")
      (node (ref "C17") (pin "2") (pinfunction "2_2") (pintype "passive"))
      (node (ref "S") (pin "6") (pinfunction "CTRL_6") (pintype "input"))
      (node (ref "SX1272") (pin "23") (pinfunction "RXTX_23") (pintype "output"))
    )
    (net (code "53") (name "S1") (class "Default")
      (node (ref "GNSS_SWITCH") (pin "3") (pinfunction "V1_3") (pintype "bidirectional"))
      (node (ref "PICO") (pin "P$20") (pinfunction "GP15_P$20") (pintype "bidirectional"))
    )
    (net (code "54") (name "S2") (class "Default")
      (node (ref "GNSS_SWITCH") (pin "2") (pinfunction "V2_2") (pintype "bidirectional"))
      (node (ref "PICO") (pin "P$19") (pinfunction "GP14_P$19") (pintype "bidirectional"))
    )
    (net (code "55") (name "SCK") (class "Default")
      (node (ref "PICO") (pin "P$4") (pinfunction "GP2_P$4") (pintype "bidirectional"))
      (node (ref "SX1272") (pin "17") (pinfunction "SCK_17") (pintype "input"))
    )
    (net (code "56") (name "VBUS") (class "Default")
      (node (ref "<-D") (pin "K") (pinfunction "K_K") (pintype "passive"))
      (node (ref "AP2112") (pin "1") (pinfunction "VIN_1") (pintype "bidirectional"))
      (node (ref "AP2112") (pin "3") (pinfunction "EN_3") (pintype "bidirectional"))
      (node (ref "C19") (pin "1") (pinfunction "1_1") (pintype "passive"))
    )
    (net (code "57") (name "VCC_RF") (class "Default")
      (node (ref "C21") (pin "2") (pinfunction "2_2") (pintype "passive"))
      (node (ref "GNSS") (pin "14") (pinfunction "VCC_RF_14") (pintype "bidirectional"))
      (node (ref "LNA") (pin "2") (pinfunction "VCC_2") (pintype "power_in"))
    )
    (net (code "58") (name "unconnected-(AP2112-ADJ{slash}NC-Pad4)") (class "Default")
      (node (ref "AP2112") (pin "4") (pinfunction "ADJ/NC_4") (pintype "bidirectional"))
    )
    (net (code "59") (name "unconnected-(GNSS-RESERVED_1-Pad15)") (class "Default")
      (node (ref "GNSS") (pin "15") (pinfunction "RESERVED_1_15") (pintype "bidirectional"))
    )
    (net (code "60") (name "unconnected-(GNSS-RESERVED_2-Pad18)") (class "Default")
      (node (ref "GNSS") (pin "18") (pinfunction "RESERVED_2_18") (pintype "bidirectional"))
    )
    (net (code "61") (name "unconnected-(GNSS-SYS_RSTN-Pad9)") (class "Default")
      (node (ref "GNSS") (pin "9") (pinfunction "SYS_RSTN_9") (pintype "bidirectional"))
    )
    (net (code "62") (name "unconnected-(GNSS-WAKE-UP-Pad5)") (class "Default")
      (node (ref "GNSS") (pin "5") (pinfunction "WAKE-UP_5") (pintype "bidirectional"))
    )
    (net (code "63") (name "unconnected-(PICO-3V3_EN-PadP$37)") (class "Default")
      (node (ref "PICO") (pin "P$37") (pinfunction "3V3_EN_P$37") (pintype "input"))
    )
    (net (code "64") (name "unconnected-(PICO-ADC_REF-PadP$35)") (class "Default")
      (node (ref "PICO") (pin "P$35") (pinfunction "ADC_REF_P$35") (pintype "input"))
    )
    (net (code "65") (name "unconnected-(PICO-GP0-PadP$1)") (class "Default")
      (node (ref "PICO") (pin "P$1") (pinfunction "GP0_P$1") (pintype "bidirectional"))
    )
    (net (code "66") (name "unconnected-(PICO-GP1-PadP$2)") (class "Default")
      (node (ref "PICO") (pin "P$2") (pinfunction "GP1_P$2") (pintype "bidirectional"))
    )
    (net (code "67") (name "unconnected-(PICO-GP9-PadP$12)") (class "Default")
      (node (ref "PICO") (pin "P$12") (pinfunction "GP9_P$12") (pintype "bidirectional"))
    )
    (net (code "68") (name "unconnected-(PICO-GP10-PadP$14)") (class "Default")
      (node (ref "PICO") (pin "P$14") (pinfunction "GP10_P$14") (pintype "bidirectional"))
    )
    (net (code "69") (name "unconnected-(PICO-GP20-PadP$26)") (class "Default")
      (node (ref "PICO") (pin "P$26") (pinfunction "GP20_P$26") (pintype "bidirectional"))
    )
    (net (code "70") (name "unconnected-(PICO-GP21-PadP$27)") (class "Default")
      (node (ref "PICO") (pin "P$27") (pinfunction "GP21_P$27") (pintype "bidirectional"))
    )
    (net (code "71") (name "unconnected-(PICO-RUN-PadP$30)") (class "Default")
      (node (ref "PICO") (pin "P$30") (pinfunction "RUN_P$30") (pintype "input"))
    )
    (net (code "72") (name "unconnected-(SX1272-RESET-Pad6)") (class "Default")
      (node (ref "SX1272") (pin "6") (pinfunction "RESET_6") (pintype "bidirectional"))
    )
    (net (code "73") (name "unconnected-(SX1272-RFO-Pad24)") (class "Default")
      (node (ref "SX1272") (pin "24") (pinfunction "RFO_24") (pintype "output"))
    )
    (net (code "74") (name "unconnected-(SX1272-RF_MOD-Pad21)") (class "Default")
      (node (ref "SX1272") (pin "21") (pinfunction "RF_MOD_21") (pintype "output"))
    )
  )
)
